# Overall_Sys_Schematic_version_2.net
KiCad netlist of a schematic drawn in EAGLE
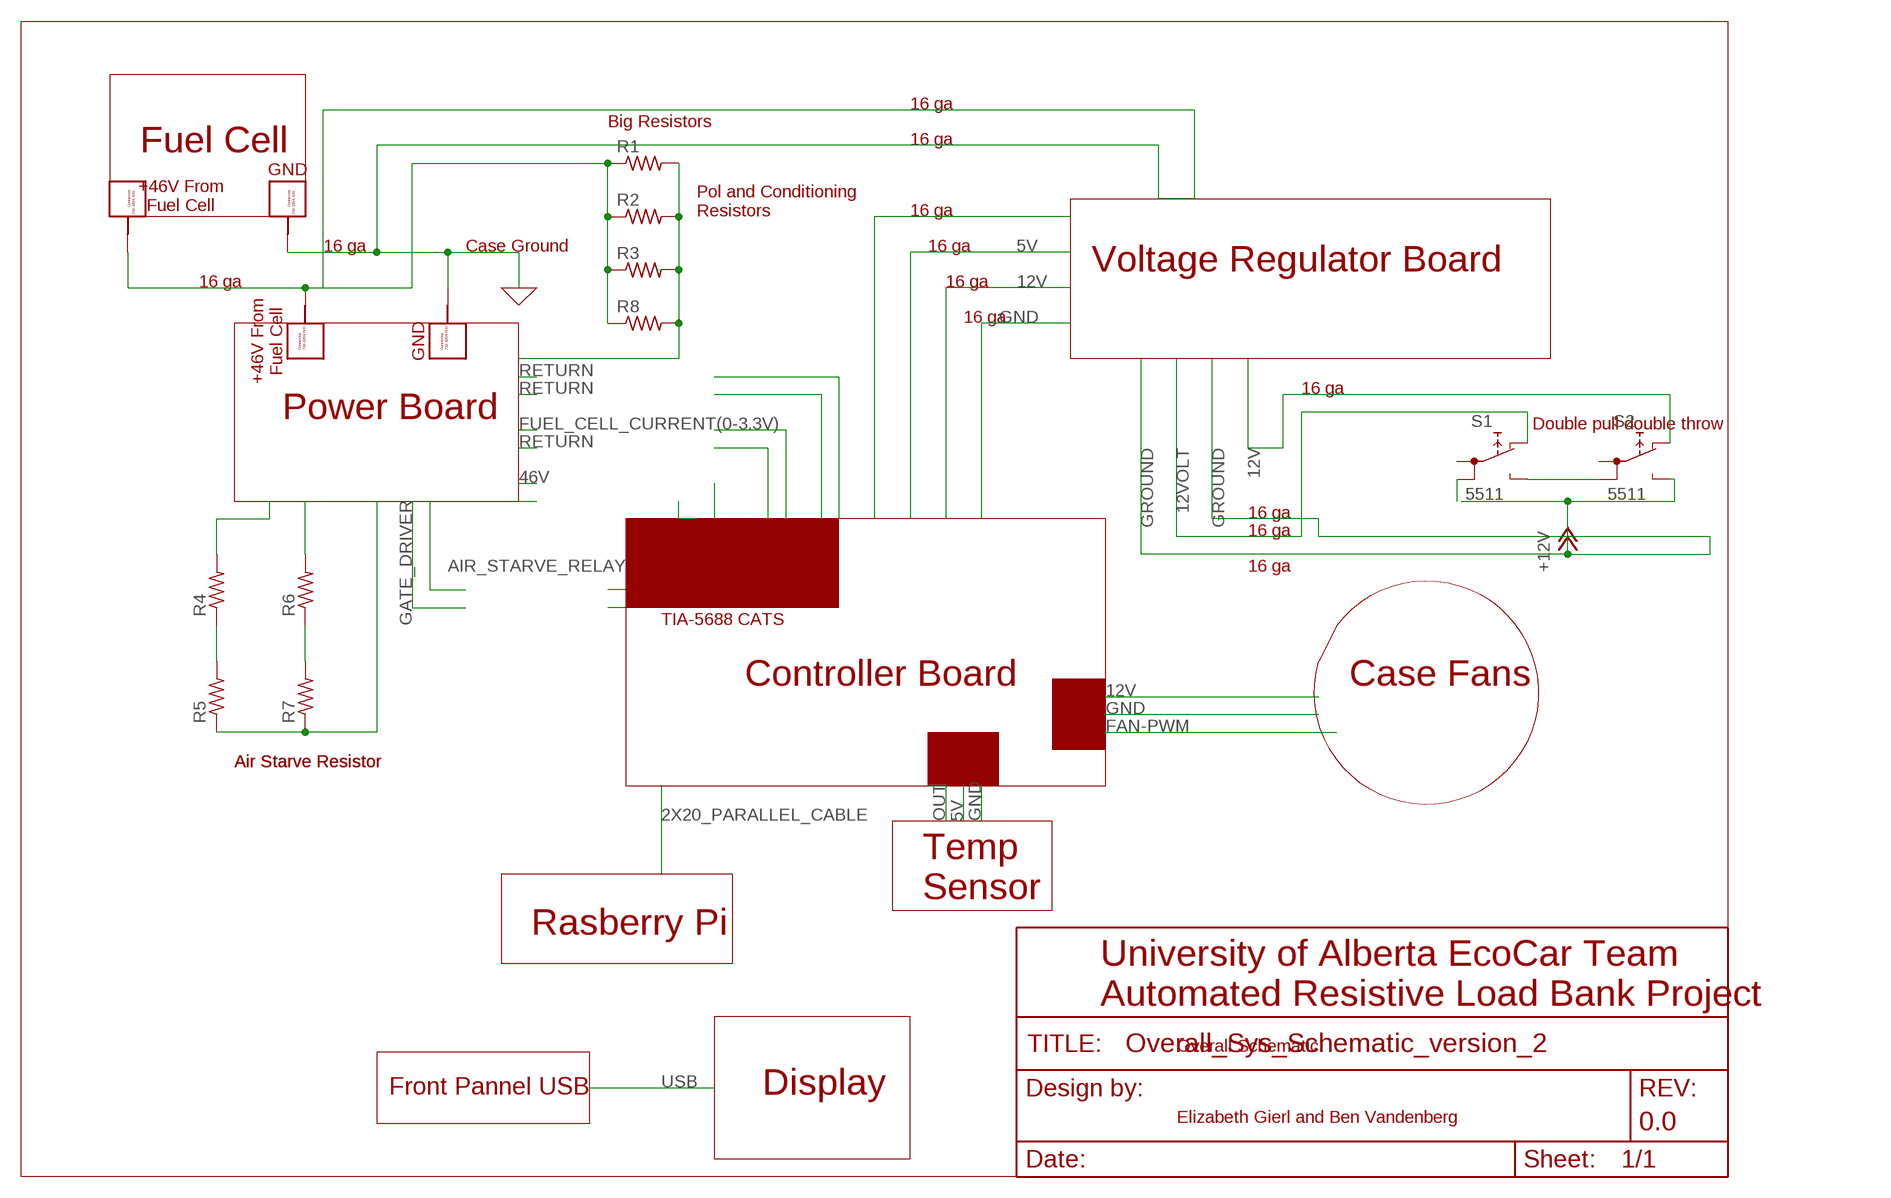
[diagram p0: schematic, sheet 1]

(export (version "E")
  (design (tool "Eeschema 10.0.6"))
  (components
    (comp (ref "FC.POS")
      (value "732-3204-ND_CONNECTOR")
      (footprint "eagle-import:732-3204-ND")
      (libsource (lib "eagle-import") (part "732-3204-ND_CONNECTOR"))
    )
    (comp (ref "FC.POS1")
      (value "732-3204-ND_CONNECTOR")
      (footprint "eagle-import:732-3204-ND")
      (libsource (lib "eagle-import") (part "732-3204-ND_CONNECTOR"))
    )
    (comp (ref "FC.POS2")
      (value "732-3204-ND_CONNECTOR")
      (footprint "eagle-import:732-3204-ND")
      (libsource (lib "eagle-import") (part "732-3204-ND_CONNECTOR"))
    )
    (comp (ref "FC.POS3")
      (value "732-3204-ND_CONNECTOR")
      (footprint "eagle-import:732-3204-ND")
      (libsource (lib "eagle-import") (part "732-3204-ND_CONNECTOR"))
    )
    (comp (ref "FRAME1")
      (value "FRAME-LETTERNO_PACKAGE")
      (footprint "eagle-import:DUMMY")
      (fields (field (name "DESIGNER") "Ben Vandenberg") (field (name "REV") "0.0"))
      (libsource (lib "eagle-import") (part "FRAME-LETTERNO_PACKAGE"))
    )
    (comp (ref "R1")
      (value "R-US_0204/2V")
      (footprint "eagle-import:0204V")
      (libsource (lib "eagle-import") (part "R-US_0204/2V"))
    )
    (comp (ref "R2")
      (value "R-US_0204/2V")
      (footprint "eagle-import:0204V")
      (libsource (lib "eagle-import") (part "R-US_0204/2V"))
    )
    (comp (ref "R3")
      (value "R-US_0204/2V")
      (footprint "eagle-import:0204V")
      (libsource (lib "eagle-import") (part "R-US_0204/2V"))
    )
    (comp (ref "R4")
      (value "R-US_0204/2V")
      (footprint "eagle-import:0204V")
      (libsource (lib "eagle-import") (part "R-US_0204/2V"))
    )
    (comp (ref "R5")
      (value "R-US_0204/2V")
      (footprint "eagle-import:0204V")
      (libsource (lib "eagle-import") (part "R-US_0204/2V"))
    )
    (comp (ref "R6")
      (value "R-US_0204/2V")
      (footprint "eagle-import:0204V")
      (libsource (lib "eagle-import") (part "R-US_0204/2V"))
    )
    (comp (ref "R7")
      (value "R-US_0204/2V")
      (footprint "eagle-import:0204V")
      (libsource (lib "eagle-import") (part "R-US_0204/2V"))
    )
    (comp (ref "R8")
      (value "R-US_0204/2V")
      (footprint "eagle-import:0204V")
      (libsource (lib "eagle-import") (part "R-US_0204/2V"))
    )
    (comp (ref "S1")
      (value "5511")
      (footprint "eagle-import:5511")
      (libsource (lib "eagle-import") (part "55?11"))
    )
    (comp (ref "S2")
      (value "5511")
      (footprint "eagle-import:5511")
      (libsource (lib "eagle-import") (part "55?11"))
    )
  )
  (nets
    (net (code "1") (name "+12V") (class "Default")
      (node (ref "S2") (pin "NO") (pinfunction "NO_NO") (pintype "passive"))
    )
    (net (code "4") (name "/12V") (class "Default")
      (node (ref "S2") (pin "NC") (pinfunction "NC_NC") (pintype "passive"))
    )
    (net (code "5") (name "/12VOLT") (class "Default")
      (node (ref "S1") (pin "NC") (pinfunction "NC_NC") (pintype "passive"))
    )
    (net (code "14") (name "GND") (class "Default")
      (node (ref "FC.POS") (pin "P$1") (pinfunction "P$1_P$1") (pintype "bidirectional"))
      (node (ref "FC.POS") (pin "P$10") (pinfunction "P$1_P$10") (pintype "bidirectional"))
      (node (ref "FC.POS") (pin "P$2") (pinfunction "P$1_P$2") (pintype "bidirectional"))
      (node (ref "FC.POS") (pin "P$3") (pinfunction "P$1_P$3") (pintype "bidirectional"))
      (node (ref "FC.POS") (pin "P$4") (pinfunction "P$1_P$4") (pintype "bidirectional"))
      (node (ref "FC.POS") (pin "P$5") (pinfunction "P$1_P$5") (pintype "bidirectional"))
      (node (ref "FC.POS") (pin "P$6") (pinfunction "P$1_P$6") (pintype "bidirectional"))
      (node (ref "FC.POS") (pin "P$7") (pinfunction "P$1_P$7") (pintype "bidirectional"))
      (node (ref "FC.POS") (pin "P$8") (pinfunction "P$1_P$8") (pintype "bidirectional"))
      (node (ref "FC.POS") (pin "P$9") (pinfunction "P$1_P$9") (pintype "bidirectional"))
      (node (ref "FC.POS1") (pin "P$1") (pinfunction "P$1_P$1") (pintype "bidirectional"))
      (node (ref "FC.POS1") (pin "P$10") (pinfunction "P$1_P$10") (pintype "bidirectional"))
      (node (ref "FC.POS1") (pin "P$2") (pinfunction "P$1_P$2") (pintype "bidirectional"))
      (node (ref "FC.POS1") (pin "P$3") (pinfunction "P$1_P$3") (pintype "bidirectional"))
      (node (ref "FC.POS1") (pin "P$4") (pinfunction "P$1_P$4") (pintype "bidirectional"))
      (node (ref "FC.POS1") (pin "P$5") (pinfunction "P$1_P$5") (pintype "bidirectional"))
      (node (ref "FC.POS1") (pin "P$6") (pinfunction "P$1_P$6") (pintype "bidirectional"))
      (node (ref "FC.POS1") (pin "P$7") (pinfunction "P$1_P$7") (pintype "bidirectional"))
      (node (ref "FC.POS1") (pin "P$8") (pinfunction "P$1_P$8") (pintype "bidirectional"))
      (node (ref "FC.POS1") (pin "P$9") (pinfunction "P$1_P$9") (pintype "bidirectional"))
      (node (ref "FC.POS2") (pin "P$1") (pinfunction "P$1_P$1") (pintype "bidirectional"))
      (node (ref "FC.POS2") (pin "P$10") (pinfunction "P$1_P$10") (pintype "bidirectional"))
      (node (ref "FC.POS2") (pin "P$2") (pinfunction "P$1_P$2") (pintype "bidirectional"))
      (node (ref "FC.POS2") (pin "P$3") (pinfunction "P$1_P$3") (pintype "bidirectional"))
      (node (ref "FC.POS2") (pin "P$4") (pinfunction "P$1_P$4") (pintype "bidirectional"))
      (node (ref "FC.POS2") (pin "P$5") (pinfunction "P$1_P$5") (pintype "bidirectional"))
      (node (ref "FC.POS2") (pin "P$6") (pinfunction "P$1_P$6") (pintype "bidirectional"))
      (node (ref "FC.POS2") (pin "P$7") (pinfunction "P$1_P$7") (pintype "bidirectional"))
      (node (ref "FC.POS2") (pin "P$8") (pinfunction "P$1_P$8") (pintype "bidirectional"))
      (node (ref "FC.POS2") (pin "P$9") (pinfunction "P$1_P$9") (pintype "bidirectional"))
      (node (ref "FC.POS3") (pin "P$1") (pinfunction "P$1_P$1") (pintype "bidirectional"))
      (node (ref "FC.POS3") (pin "P$10") (pinfunction "P$1_P$10") (pintype "bidirectional"))
      (node (ref "FC.POS3") (pin "P$2") (pinfunction "P$1_P$2") (pintype "bidirectional"))
      (node (ref "FC.POS3") (pin "P$3") (pinfunction "P$1_P$3") (pintype "bidirectional"))
      (node (ref "FC.POS3") (pin "P$4") (pinfunction "P$1_P$4") (pintype "bidirectional"))
      (node (ref "FC.POS3") (pin "P$5") (pinfunction "P$1_P$5") (pintype "bidirectional"))
      (node (ref "FC.POS3") (pin "P$6") (pinfunction "P$1_P$6") (pintype "bidirectional"))
      (node (ref "FC.POS3") (pin "P$7") (pinfunction "P$1_P$7") (pintype "bidirectional"))
      (node (ref "FC.POS3") (pin "P$8") (pinfunction "P$1_P$8") (pintype "bidirectional"))
      (node (ref "FC.POS3") (pin "P$9") (pinfunction "P$1_P$9") (pintype "bidirectional"))
      (node (ref "R1") (pin "1") (pinfunction "1_1") (pintype "passive"))
      (node (ref "R2") (pin "1") (pinfunction "1_1") (pintype "passive"))
      (node (ref "R3") (pin "1") (pinfunction "1_1") (pintype "passive"))
      (node (ref "R8") (pin "1") (pinfunction "1_1") (pintype "passive"))
    )
    (net (code "15") (name "Net-(R1-Pad2)") (class "Default")
      (node (ref "R1") (pin "2") (pinfunction "2_2") (pintype "passive"))
      (node (ref "R2") (pin "2") (pinfunction "2_2") (pintype "passive"))
      (node (ref "R3") (pin "2") (pinfunction "2_2") (pintype "passive"))
      (node (ref "R8") (pin "2") (pinfunction "2_2") (pintype "passive"))
    )
    (net (code "16") (name "Net-(R4-Pad1)") (class "Default")
      (node (ref "R4") (pin "1") (pinfunction "1_1") (pintype "passive"))
      (node (ref "R5") (pin "2") (pinfunction "2_2") (pintype "passive"))
    )
    (net (code "17") (name "Net-(R5-Pad1)") (class "Default")
      (node (ref "R5") (pin "1") (pinfunction "1_1") (pintype "passive"))
      (node (ref "R7") (pin "1") (pinfunction "1_1") (pintype "passive"))
    )
    (net (code "18") (name "Net-(R6-Pad1)") (class "Default")
      (node (ref "R6") (pin "1") (pinfunction "1_1") (pintype "passive"))
      (node (ref "R7") (pin "2") (pinfunction "2_2") (pintype "passive"))
    )
    (net (code "19") (name "Net-(S1-PadNO)") (class "Default")
      (node (ref "S1") (pin "NO") (pinfunction "NO_NO") (pintype "passive"))
      (node (ref "S2") (pin "1B") (pinfunction "1B_1B") (pintype "passive"))
    )
    (net (code "20") (name "unconnected-(R4-Pad2)") (class "Default")
      (node (ref "R4") (pin "2") (pinfunction "2_2") (pintype "passive"))
    )
    (net (code "21") (name "unconnected-(R6-Pad2)") (class "Default")
      (node (ref "R6") (pin "2") (pinfunction "2_2") (pintype "passive"))
    )
    (net (code "22") (name "unconnected-(S1-Pad1A)") (class "Default")
      (node (ref "S1") (pin "1A") (pinfunction "1A_1A") (pintype "passive"))
    )
    (net (code "23") (name "unconnected-(S1-Pad1B)") (class "Default")
      (node (ref "S1") (pin "1B") (pinfunction "1B_1B") (pintype "passive"))
    )
    (net (code "24") (name "unconnected-(S2-Pad1A)") (class "Default")
      (node (ref "S2") (pin "1A") (pinfunction "1A_1A") (pintype "passive"))
    )
  )
)
